# RTC.net
KiCad netlist of a schematic drawn in Altium Designer
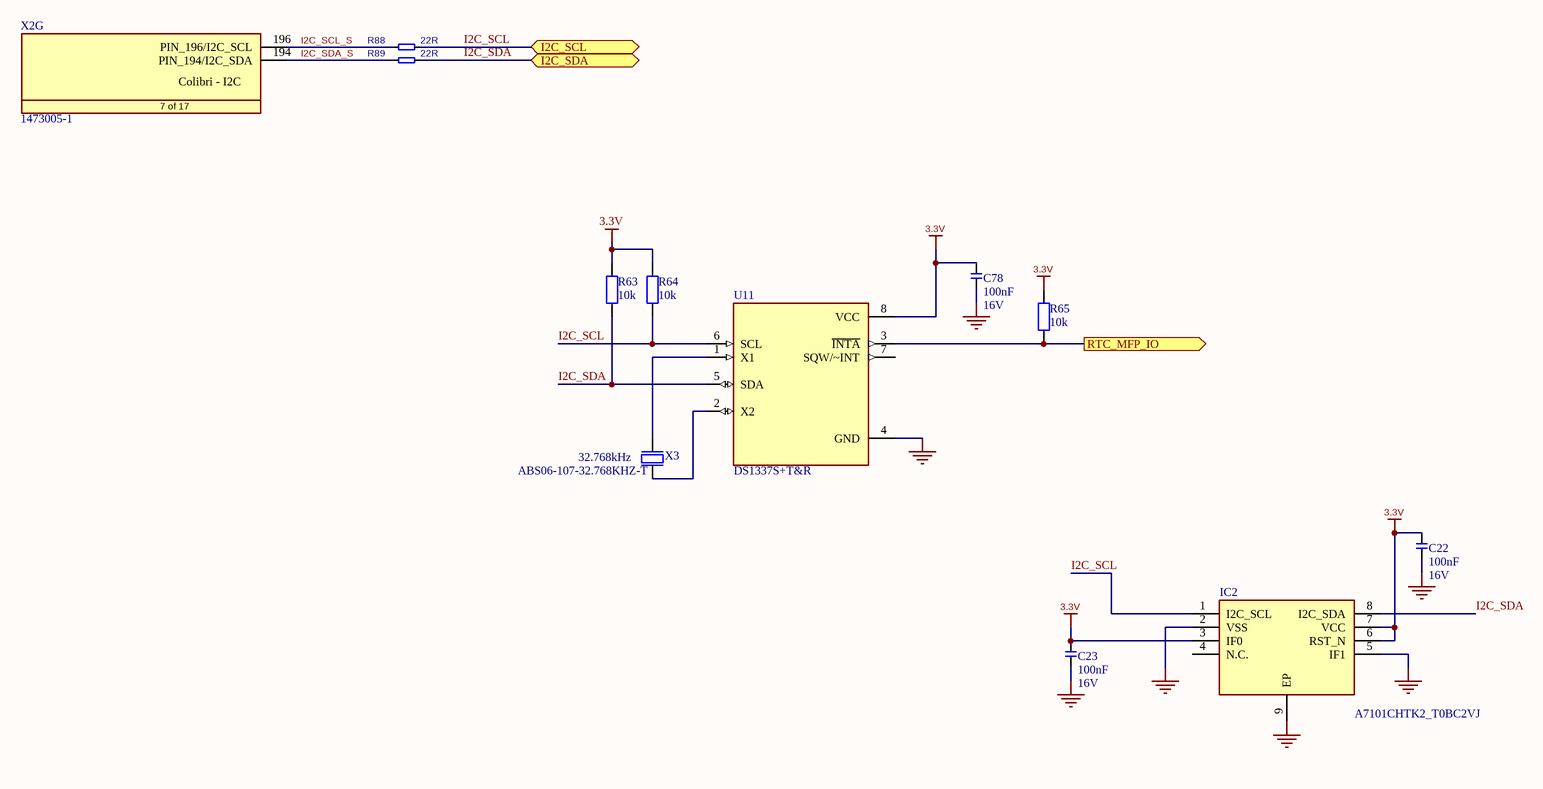
[diagram p0: RTC.SchDoc]

(export (version "E")
  (design (tool "Eeschema 10.0.6"))
  (components
    (comp (ref "C22")
      (value "100nF")
      (footprint "T_CAPC0603X33N")
      (description "Capacitor Ceramic X7R 100nF 16V 10% 0603")
      (fields (field (name "TOLERANCE") "10%") (field (name "RATING") "16V"))
      (libsource (lib "Iris") (part "C-X7R-100nF-16V-10%-0603"))
    )
    (comp (ref "C23")
      (value "100nF")
      (footprint "T_CAPC0603X33N")
      (description "Capacitor Ceramic X7R 100nF 16V 10% 0603")
      (fields (field (name "TOLERANCE") "10%") (field (name "RATING") "16V"))
      (libsource (lib "Iris") (part "C-X7R-100nF-16V-10%-0603"))
    )
    (comp (ref "C78")
      (value "100nF")
      (footprint "T_CAPC0603X33N")
      (description "Capacitor Ceramic X7R 100nF 16V 10% 0603")
      (fields (field (name "TOLERANCE") "10%") (field (name "RATING") "16V"))
      (libsource (lib "Iris") (part "C-X7R-100nF-16V-10%-0603"))
    )
    (comp (ref "IC2")
      (value "A7101CHTK2_T0BC2VJ")
      (footprint "SamacSys:SON80P400X400X100-9N-D")
      (description "Integrated Circuit")
      (fields
        (field (name "MOUSER2 PART NUMBER") "771-A7101CHTKT0BC2VJ")
        (field (name "MANUFACTURER_PART_NUMBER") "A7101CHTK2/T0BC2VJ")
      )
      (libsource (lib "*") (part "A7101CHTK2_T0BC2VJ"))
    )
    (comp (ref "R63")
      (value "10k")
      (footprint "RESC1608X50N")
      (description "RES SMD 10K OHM 1% 1/8W 0805")
      (libsource (lib "altium-import") (part "root_1_CMP-1909346-3_"))
    )
    (comp (ref "R64")
      (value "10k")
      (footprint "RESC1608X50N")
      (description "RES SMD 10K OHM 1% 1/8W 0805")
      (libsource (lib "altium-import") (part "root_1_CMP-1909346-3_"))
    )
    (comp (ref "R65")
      (value "10k")
      (footprint "RESC1608X50N")
      (description "RES SMD 10K OHM 1% 1/8W 0805")
      (libsource (lib "altium-import") (part "root_1_CMP-1909346-3_"))
    )
    (comp (ref "R88")
      (value "22R")
      (footprint "RESC1005X40N")
      (description "Resistor 22 ohm 63mW 5% 0402")
      (fields (field (name "TOLERANCE") "5%"))
      (libsource (lib "Iris") (part "R-22R-63mW-5%-0402"))
    )
    (comp (ref "R89")
      (value "22R")
      (footprint "RESC1005X40N")
      (description "Resistor 22 ohm 63mW 5% 0402")
      (fields (field (name "TOLERANCE") "5%"))
      (libsource (lib "Iris") (part "R-22R-63mW-5%-0402"))
    )
    (comp (ref "U11")
      (value "DS1337S+T&R")
      (footprint "SOIC127P600X175-8N")
      (description "Real Time Clock (RTC) IC Clock/Calendar IÂ²C, 2-Wire Serial 8-SOIC (0.154, 3.90mm Width)")
      (fields (field (name "MP") "DS1337S+T&amp;R") (field (name "DIGI-KEY_PART_NUMBER") "DS1337S+T&RCT-ND"))
      (libsource (lib "Inlib") (part "DS1337S+T&R"))
    )
    (comp (ref "X2")
      (value "1473005-1")
      (footprint "T_Tyco_1473005-1")
      (description "SODIMM Connector")
      (fields (field (name "MANUFACTURER PART NO.") "1473005-1"))
      (libsource (lib "Iris") (part "CON-Tyco-1473005-1-200-0.6mm"))
    )
    (comp (ref "X3")
      (value "32.768kHz")
      (footprint "ABS06")
      (description "XTAL SMD 2016, 32MHz, Cl=8pF, Tol: ±10ppm, Stab: ±10ppm")
      (fields
        (field (name "PART NUMBER") "XTAL_SMD2016_32MHz_12pF")
        (field (name "MANUFACTURER") "AVX Corp/Kyocera Corp")
        (field (name "MANUFACTURER PN") "ABS06-107-32.768KHZ-T")
        (field (name "PUBLISHER") "Nordic Semiconductor")
      )
      (libsource (lib "Nordic Discrete DB") (part "XTAL_4-pin_grounded"))
    )
  )
  (nets
    (net (code "1") (name "/I2C_SCL") (class "Default")
      (node (ref "IC2") (pin "1") (pinfunction "I2C_SCL_1") (pintype "passive"))
      (node (ref "R64") (pin "1") (pinfunction "1_1") (pintype "passive"))
      (node (ref "R88") (pin "2") (pinfunction "2_2") (pintype "passive"))
      (node (ref "U11") (pin "6") (pinfunction "SCL_6") (pintype "input"))
    )
    (net (code "2") (name "/I2C_SCL_S") (class "Default")
      (node (ref "R88") (pin "1") (pinfunction "1_1") (pintype "passive"))
      (node (ref "X2") (pin "196") (pinfunction "PIN_196/I2C_SCL_196") (pintype "passive"))
    )
    (net (code "3") (name "/I2C_SDA") (class "Default")
      (node (ref "IC2") (pin "8") (pinfunction "I2C_SDA_8") (pintype "passive"))
      (node (ref "R63") (pin "1") (pinfunction "1_1") (pintype "passive"))
      (node (ref "R89") (pin "2") (pinfunction "2_2") (pintype "passive"))
      (node (ref "U11") (pin "5") (pinfunction "SDA_5") (pintype "bidirectional"))
    )
    (net (code "4") (name "/I2C_SDA_S") (class "Default")
      (node (ref "R89") (pin "1") (pinfunction "1_1") (pintype "passive"))
      (node (ref "X2") (pin "194") (pinfunction "PIN_194/I2C_SDA_194") (pintype "passive"))
    )
    (net (code "5") (name "/RTC_MFP_IO") (class "Default")
      (node (ref "R65") (pin "1") (pinfunction "1_1") (pintype "passive"))
      (node (ref "U11") (pin "3") (pinfunction "~{INTA}_3") (pintype "output"))
    )
    (net (code "6") (name "3.3V") (class "Default")
      (node (ref "C22") (pin "2") (pinfunction "2_2") (pintype "passive"))
      (node (ref "C23") (pin "2") (pinfunction "2_2") (pintype "passive"))
      (node (ref "C78") (pin "2") (pinfunction "2_2") (pintype "passive"))
      (node (ref "IC2") (pin "3") (pinfunction "IF0_3") (pintype "passive"))
      (node (ref "IC2") (pin "6") (pinfunction "RST_N_6") (pintype "passive"))
      (node (ref "IC2") (pin "7") (pinfunction "VCC_7") (pintype "passive"))
      (node (ref "R63") (pin "2") (pinfunction "2_2") (pintype "passive"))
      (node (ref "R64") (pin "2") (pinfunction "2_2") (pintype "passive"))
      (node (ref "R65") (pin "2") (pinfunction "2_2") (pintype "passive"))
      (node (ref "U11") (pin "8") (pinfunction "VCC_8") (pintype "power_in"))
    )
    (net (code "7") (name "GND") (class "Default")
      (node (ref "C22") (pin "1") (pinfunction "1_1") (pintype "passive"))
      (node (ref "C23") (pin "1") (pinfunction "1_1") (pintype "passive"))
      (node (ref "C78") (pin "1") (pinfunction "1_1") (pintype "passive"))
      (node (ref "IC2") (pin "2") (pinfunction "VSS_2") (pintype "passive"))
      (node (ref "IC2") (pin "5") (pinfunction "IF1_5") (pintype "passive"))
      (node (ref "IC2") (pin "9") (pinfunction "EP_9") (pintype "passive"))
      (node (ref "U11") (pin "4") (pinfunction "GND_4") (pintype "power_in"))
    )
    (net (code "8") (name "Net-(U11-X1)") (class "Default")
      (node (ref "U11") (pin "1") (pinfunction "X1_1") (pintype "input"))
      (node (ref "X3") (pin "1") (pinfunction "inp_1") (pintype "passive"))
    )
    (net (code "9") (name "Net-(U11-X2)") (class "Default")
      (node (ref "U11") (pin "2") (pinfunction "X2_2") (pintype "bidirectional"))
      (node (ref "X3") (pin "2") (pinfunction "out_2") (pintype "passive"))
    )
    (net (code "10") (name "unconnected-(IC2-N.C.-Pad4)") (class "Default")
      (node (ref "IC2") (pin "4") (pinfunction "N.C._4") (pintype "passive"))
    )
    (net (code "11") (name "unconnected-(U11-SQW{slash}~INT-Pad7)") (class "Default")
      (node (ref "U11") (pin "7") (pinfunction "SQW/~INT_7") (pintype "output"))
    )
  )
)
